# Emmelie-v3_2.net
KiCad netlist of a schematic drawn in EAGLE
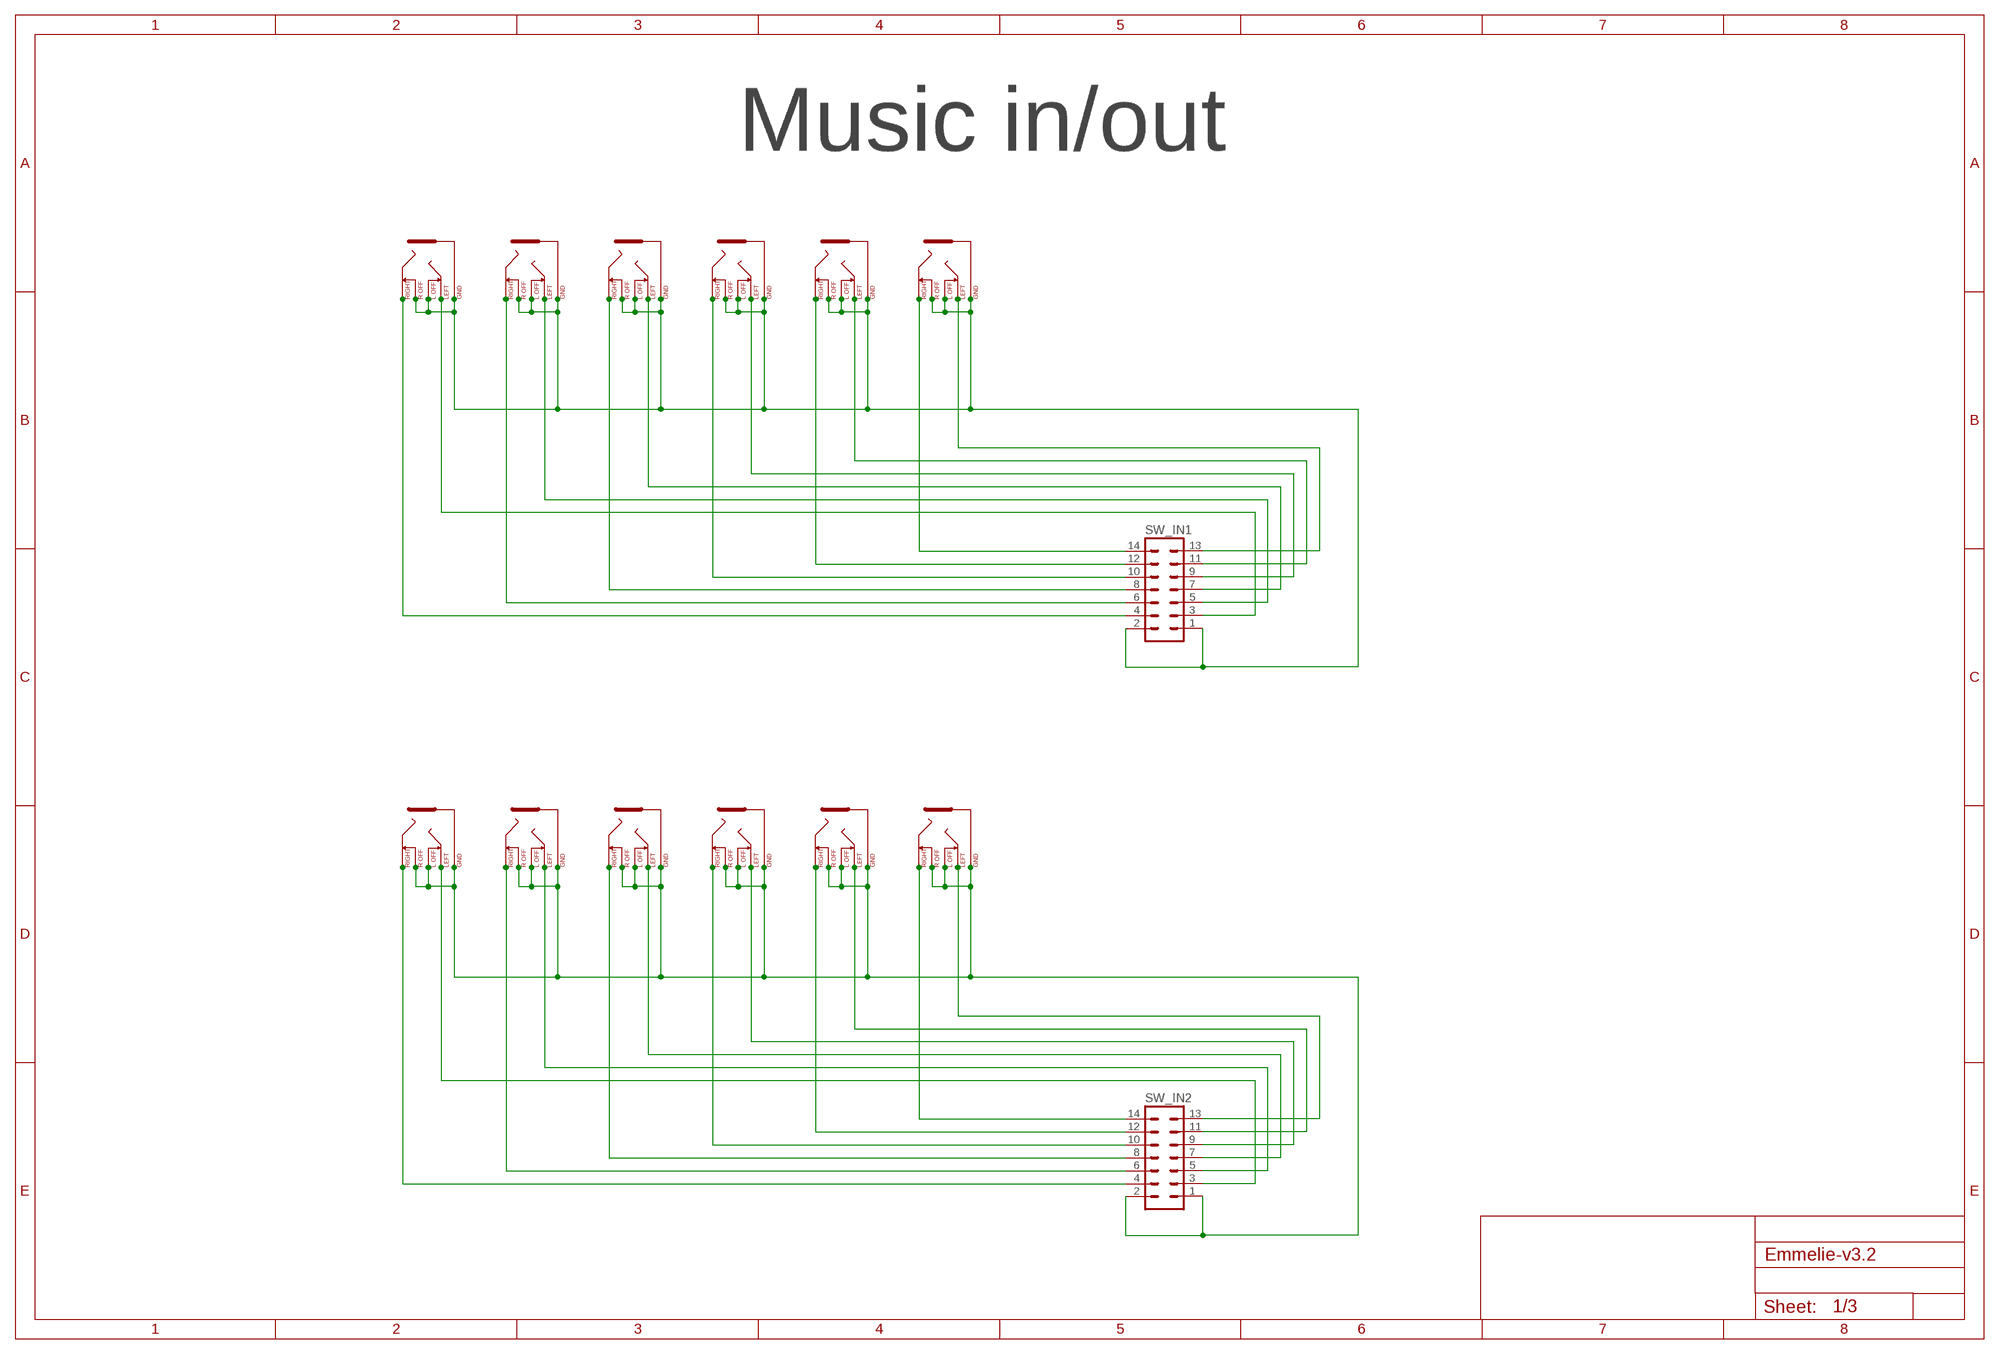
[diagram p0: schematic, sheet 1]
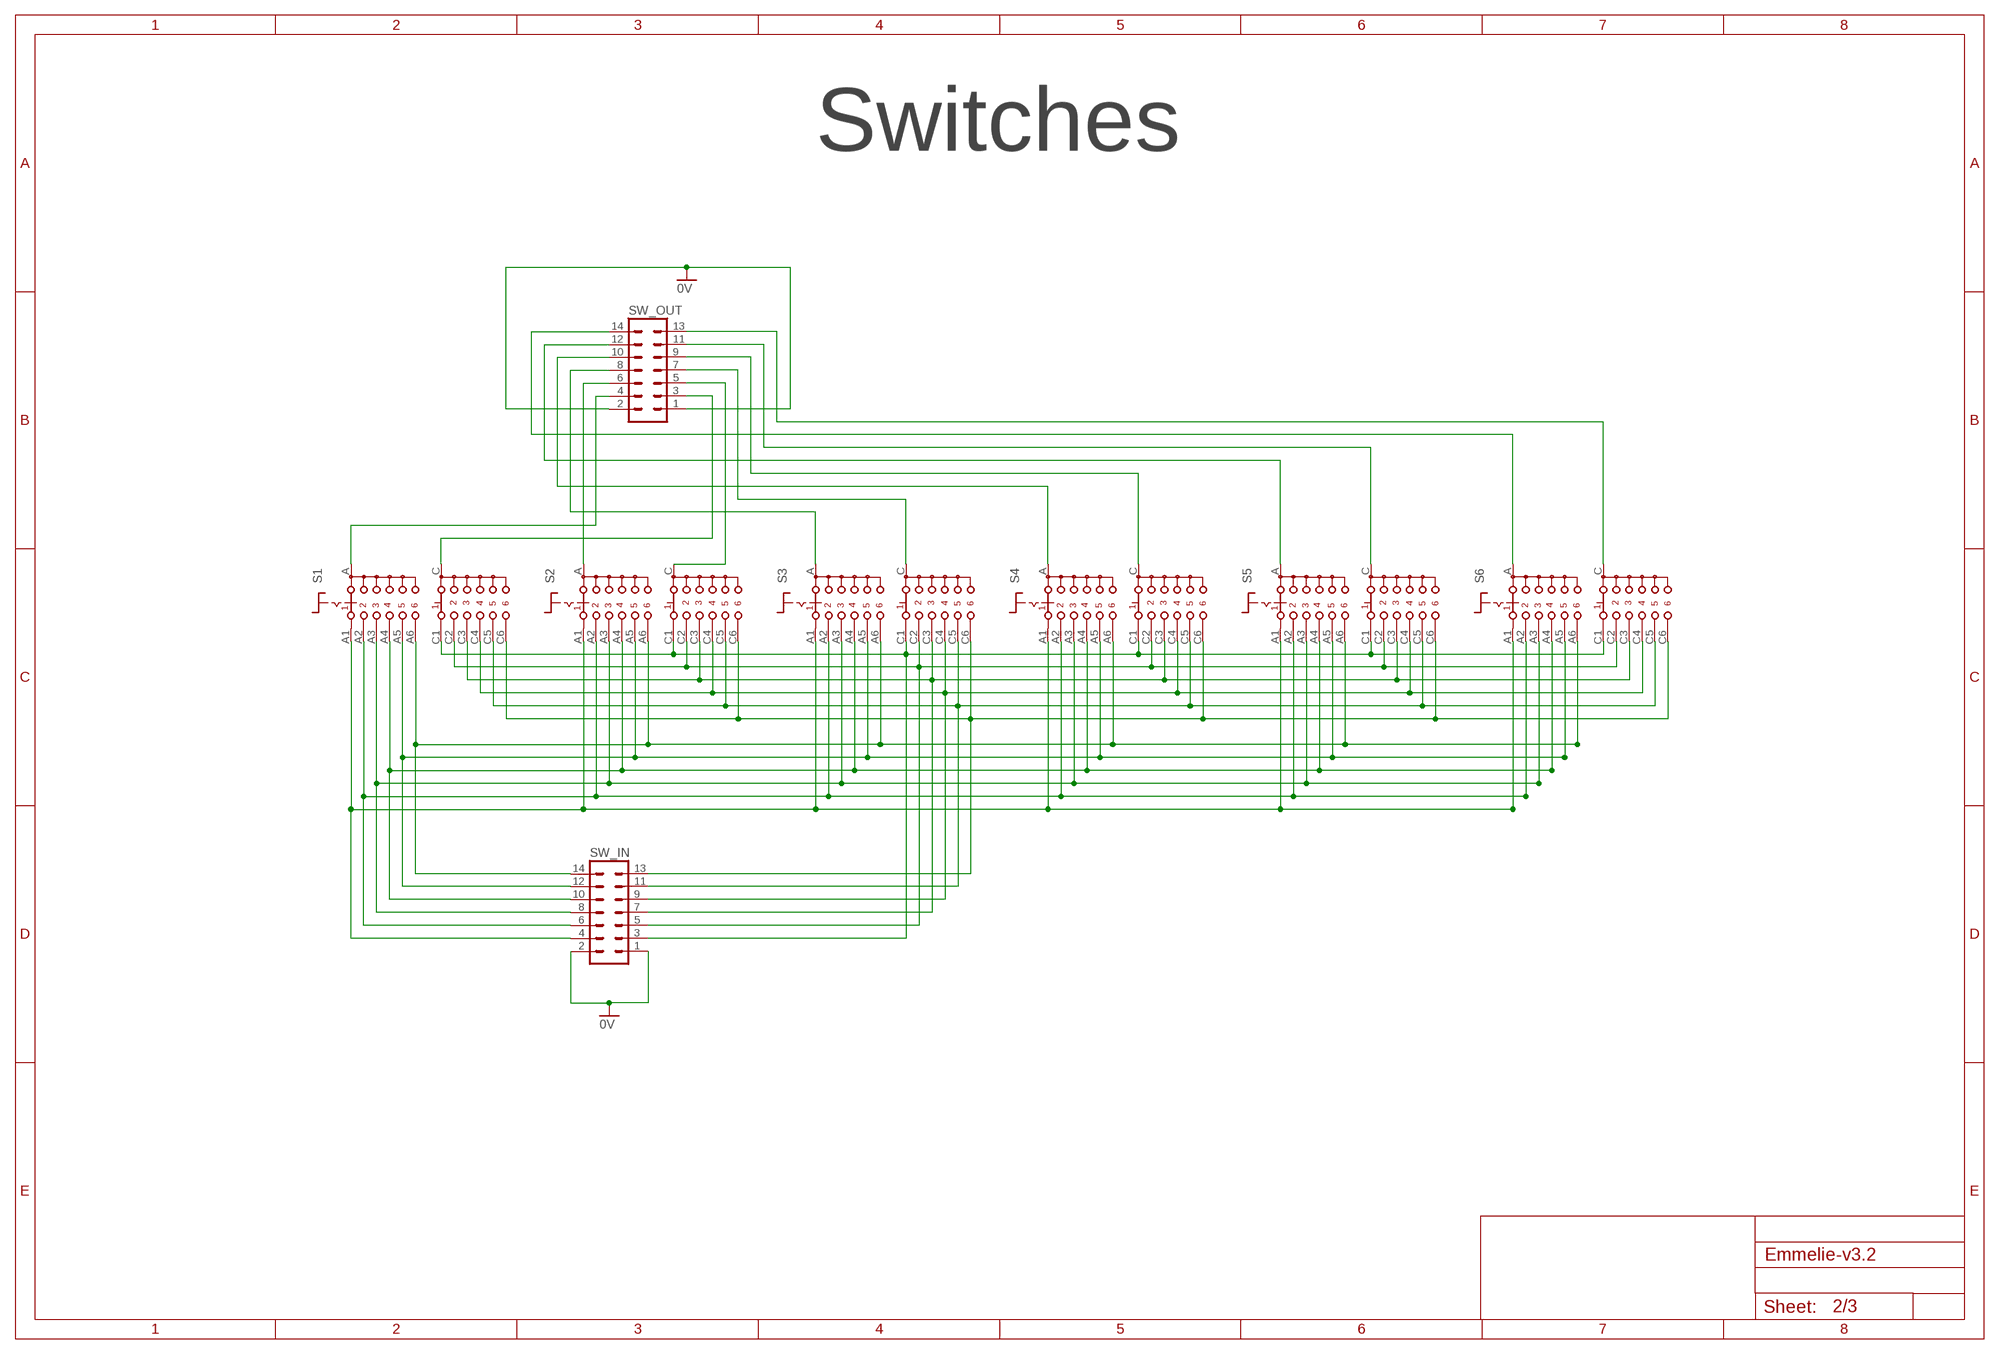
[diagram p1: schematic, sheet 2]
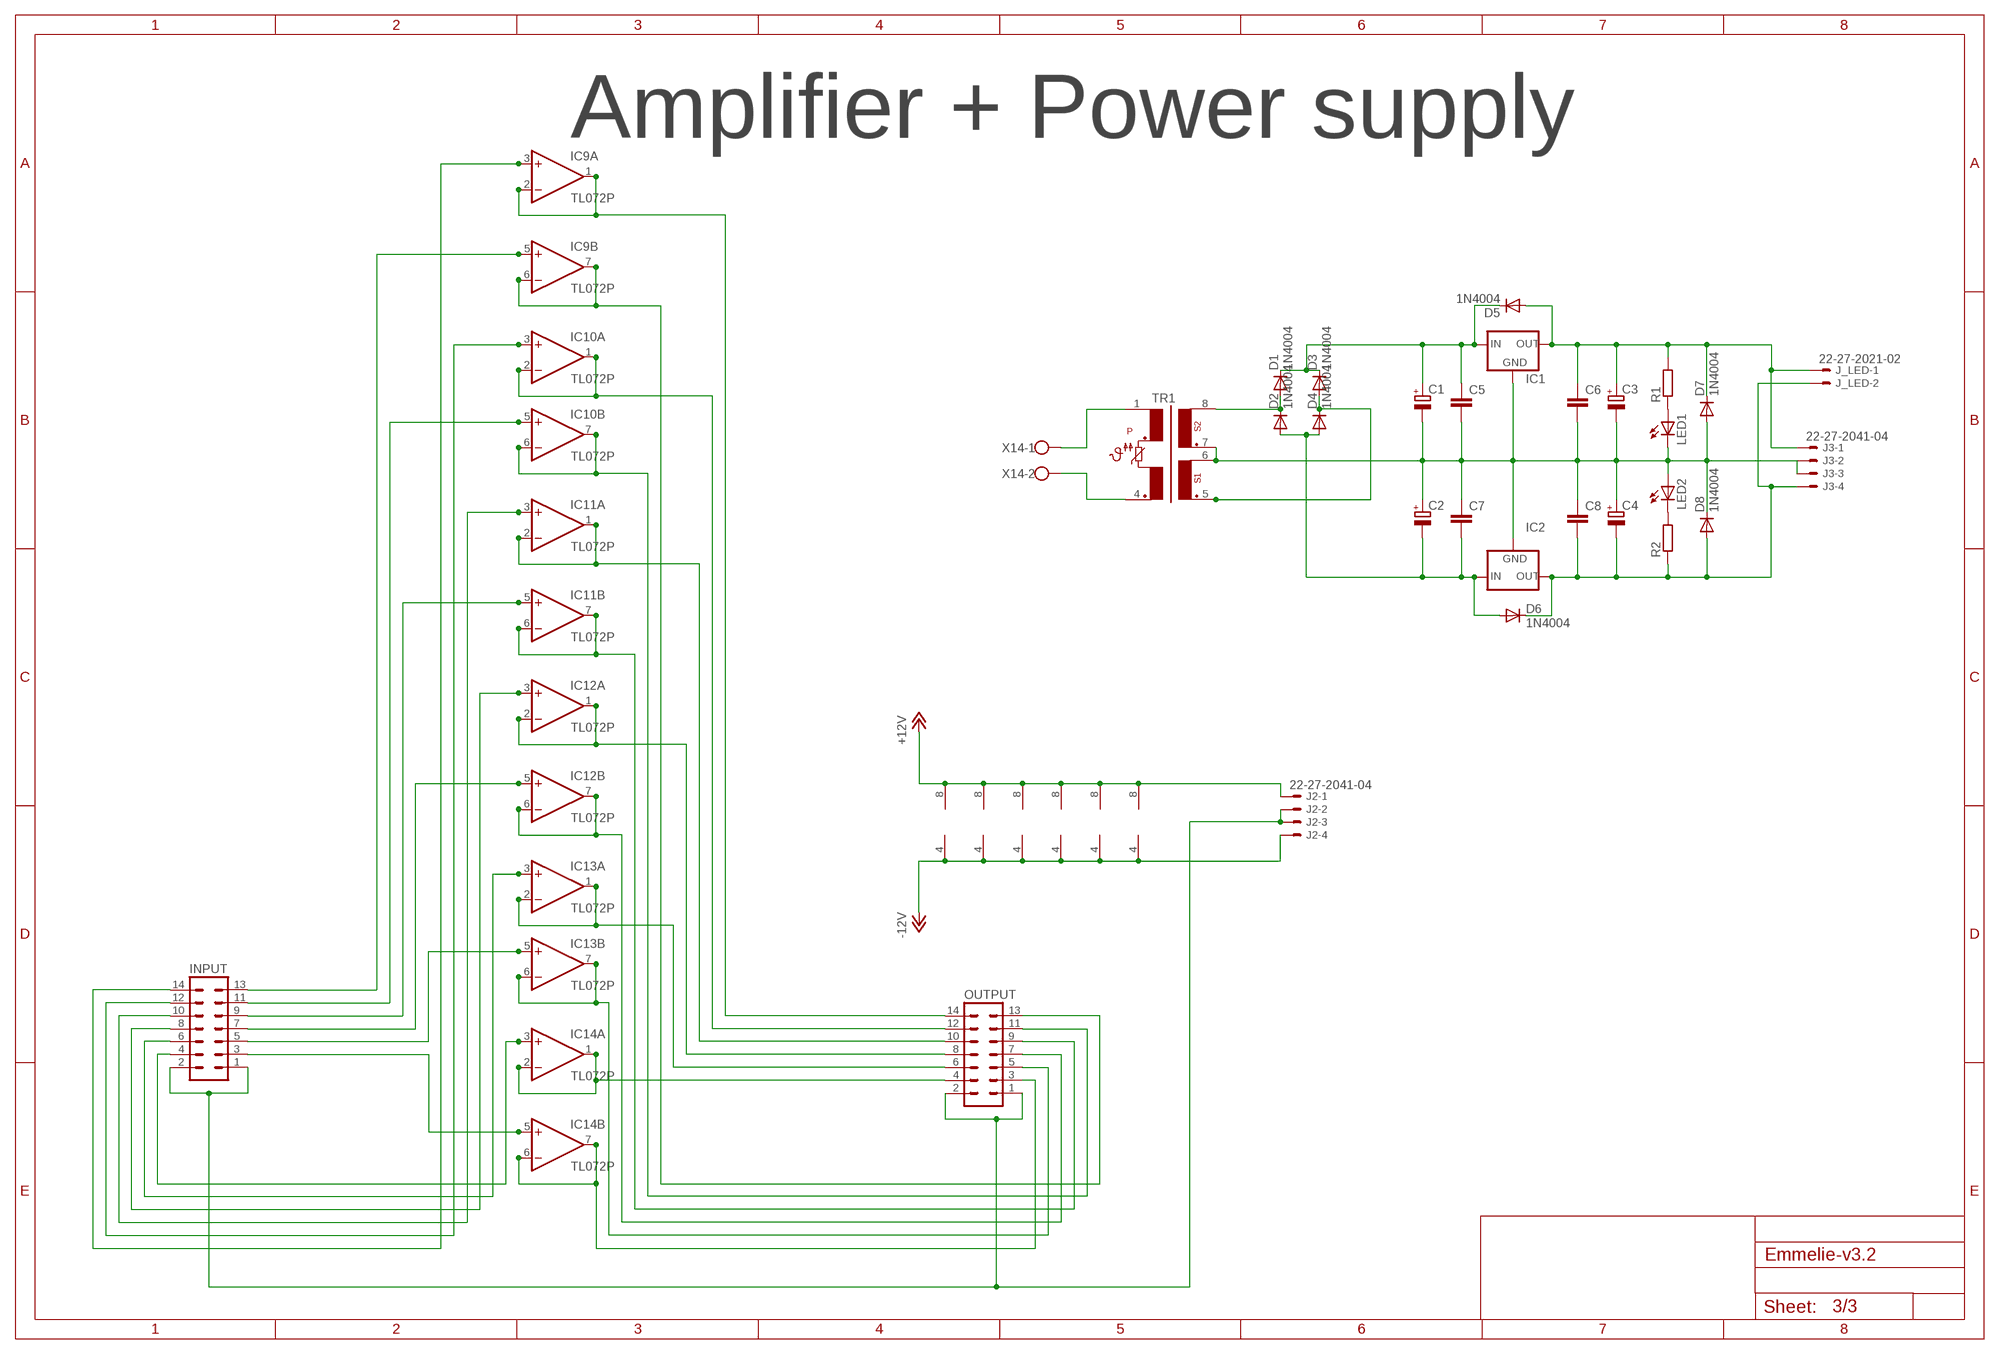
[diagram p2: schematic, sheet 3]

(export (version "E")
  (design (tool "Eeschema 10.0.6"))
  (components
    (comp (ref "C1")
      (value "CPOL-EUE5-13")
      (footprint "eagle-import:E5-13")
      (libsource (lib "eagle-import") (part "resistor_CPOL-EUE5-13"))
    )
    (comp (ref "C2")
      (value "CPOL-EUE5-13")
      (footprint "eagle-import:E5-13")
      (libsource (lib "eagle-import") (part "resistor_CPOL-EUE5-13"))
    )
    (comp (ref "C3")
      (value "CPOL-EUE2.5-7")
      (footprint "eagle-import:E2,5-7")
      (libsource (lib "eagle-import") (part "CPOL-EUE2.5-7"))
    )
    (comp (ref "C4")
      (value "CPOL-EUE2.5-7")
      (footprint "eagle-import:E2,5-7")
      (libsource (lib "eagle-import") (part "CPOL-EUE2.5-7"))
    )
    (comp (ref "C5")
      (value "C-EU050-075X075")
      (footprint "eagle-import:C050-075X075")
      (libsource (lib "eagle-import") (part "C-EU050-075X075"))
    )
    (comp (ref "C6")
      (value "C-EU050-075X075")
      (footprint "eagle-import:C050-075X075")
      (libsource (lib "eagle-import") (part "C-EU050-075X075"))
    )
    (comp (ref "C7")
      (value "C-EU050-075X075")
      (footprint "eagle-import:C050-075X075")
      (libsource (lib "eagle-import") (part "C-EU050-075X075"))
    )
    (comp (ref "C8")
      (value "C-EU050-075X075")
      (footprint "eagle-import:C050-075X075")
      (libsource (lib "eagle-import") (part "C-EU050-075X075"))
    )
    (comp (ref "D1")
      (value "1N4004")
      (footprint "eagle-import:DO41-10")
      (libsource (lib "eagle-import") (part "1N4004"))
    )
    (comp (ref "D2")
      (value "1N4004")
      (footprint "eagle-import:DO41-10")
      (libsource (lib "eagle-import") (part "1N4004"))
    )
    (comp (ref "D3")
      (value "1N4004")
      (footprint "eagle-import:DO41-10")
      (libsource (lib "eagle-import") (part "1N4004"))
    )
    (comp (ref "D4")
      (value "1N4004")
      (footprint "eagle-import:DO41-10")
      (libsource (lib "eagle-import") (part "1N4004"))
    )
    (comp (ref "D5")
      (value "1N4004")
      (footprint "eagle-import:DO41-10")
      (libsource (lib "eagle-import") (part "1N4004"))
    )
    (comp (ref "D6")
      (value "1N4004")
      (footprint "eagle-import:DO41-10")
      (libsource (lib "eagle-import") (part "1N4004"))
    )
    (comp (ref "D7")
      (value "1N4004")
      (footprint "eagle-import:DO41-10")
      (libsource (lib "eagle-import") (part "1N4004"))
    )
    (comp (ref "D8")
      (value "1N4004")
      (footprint "eagle-import:DO41-10")
      (libsource (lib "eagle-import") (part "1N4004"))
    )
    (comp (ref "IC1")
      (value "78XXS")
      (footprint "eagle-import:78XXS")
      (libsource (lib "eagle-import") (part "78XXS"))
    )
    (comp (ref "IC2")
      (value "79XXS")
      (footprint "eagle-import:79XXS")
      (libsource (lib "eagle-import") (part "79XXS"))
    )
    (comp (ref "IC9")
      (value "TL072P")
      (footprint "eagle-import:DIL08")
      (libsource (lib "eagle-import") (part "TL072P"))
    )
    (comp (ref "IC10")
      (value "TL072P")
      (footprint "eagle-import:DIL08")
      (libsource (lib "eagle-import") (part "TL072P"))
    )
    (comp (ref "IC11")
      (value "TL072P")
      (footprint "eagle-import:DIL08")
      (libsource (lib "eagle-import") (part "TL072P"))
    )
    (comp (ref "IC12")
      (value "TL072P")
      (footprint "eagle-import:DIL08")
      (libsource (lib "eagle-import") (part "TL072P"))
    )
    (comp (ref "IC13")
      (value "TL072P")
      (footprint "eagle-import:DIL08")
      (libsource (lib "eagle-import") (part "TL072P"))
    )
    (comp (ref "IC14")
      (value "TL072P")
      (footprint "eagle-import:DIL08")
      (libsource (lib "eagle-import") (part "TL072P"))
    )
    (comp (ref "INPUT")
      (value "ML14")
      (footprint "eagle-import:ML14")
      (libsource (lib "eagle-import") (part "ML14"))
    )
    (comp (ref "J2")
      (value "22-27-2041-04")
      (footprint "eagle-import:6410-04")
      (libsource (lib "eagle-import") (part "22-?-0427-2041"))
    )
    (comp (ref "J3")
      (value "22-27-2041-04")
      (footprint "eagle-import:6410-04")
      (libsource (lib "eagle-import") (part "22-?-0427-2041"))
    )
    (comp (ref "J_LED")
      (value "22-27-2021-02")
      (footprint "eagle-import:6410-02")
      (libsource (lib "eagle-import") (part "22-?-0227-2021"))
    )
    (comp (ref "LED1")
      (value "LED5MM")
      (footprint "eagle-import:LED5MM")
      (libsource (lib "eagle-import") (part "LED5MM"))
    )
    (comp (ref "LED2")
      (value "LED5MM")
      (footprint "eagle-import:LED5MM")
      (libsource (lib "eagle-import") (part "LED5MM"))
    )
    (comp (ref "OUTPUT")
      (value "ML14")
      (footprint "eagle-import:ML14")
      (libsource (lib "eagle-import") (part "ML14"))
    )
    (comp (ref "R1")
      (value "R-EU_0207/15")
      (footprint "eagle-import:0207_15")
      (libsource (lib "eagle-import") (part "R-EU_0207/15"))
    )
    (comp (ref "R2")
      (value "R-EU_0207/15")
      (footprint "eagle-import:0207_15")
      (libsource (lib "eagle-import") (part "R-EU_0207/15"))
    )
    (comp (ref "TR1")
      (value "FLE04-06")
      (footprint "eagle-import:FLE04-06")
      (libsource (lib "eagle-import") (part "FLE04-06"))
    )
    (comp (ref "X14")
      (value "W237-02P")
      (footprint "eagle-import:W237-132")
      (libsource (lib "eagle-import") (part "W237-02P"))
    )
    (comp (ref "SW_IN1")
      (value "ML14")
      (footprint "eagle-import:ML14")
      (libsource (lib "eagle-import") (part "ML14"))
    )
    (comp (ref "SW_IN2")
      (value "ML14")
      (footprint "eagle-import:ML14")
      (libsource (lib "eagle-import") (part "ML14"))
    )
    (comp (ref "U$1")
      (value "KLINKE3,5")
      (footprint "eagle-import:KLINKE3,5")
      (libsource (lib "eagle-import") (part "KLINKE3,5"))
    )
    (comp (ref "U$2")
      (value "KLINKE3,5")
      (footprint "eagle-import:KLINKE3,5")
      (libsource (lib "eagle-import") (part "KLINKE3,5"))
    )
    (comp (ref "U$3")
      (value "KLINKE3,5")
      (footprint "eagle-import:KLINKE3,5")
      (libsource (lib "eagle-import") (part "KLINKE3,5"))
    )
    (comp (ref "U$4")
      (value "KLINKE3,5")
      (footprint "eagle-import:KLINKE3,5")
      (libsource (lib "eagle-import") (part "KLINKE3,5"))
    )
    (comp (ref "U$5")
      (value "KLINKE3,5")
      (footprint "eagle-import:KLINKE3,5")
      (libsource (lib "eagle-import") (part "KLINKE3,5"))
    )
    (comp (ref "U$6")
      (value "KLINKE3,5")
      (footprint "eagle-import:KLINKE3,5")
      (libsource (lib "eagle-import") (part "KLINKE3,5"))
    )
    (comp (ref "U$7")
      (value "KLINKE3,5")
      (footprint "eagle-import:KLINKE3,5")
      (libsource (lib "eagle-import") (part "KLINKE3,5"))
    )
    (comp (ref "U$8")
      (value "KLINKE3,5")
      (footprint "eagle-import:KLINKE3,5")
      (libsource (lib "eagle-import") (part "KLINKE3,5"))
    )
    (comp (ref "U$9")
      (value "KLINKE3,5")
      (footprint "eagle-import:KLINKE3,5")
      (libsource (lib "eagle-import") (part "KLINKE3,5"))
    )
    (comp (ref "U$10")
      (value "KLINKE3,5")
      (footprint "eagle-import:KLINKE3,5")
      (libsource (lib "eagle-import") (part "KLINKE3,5"))
    )
    (comp (ref "U$11")
      (value "KLINKE3,5")
      (footprint "eagle-import:KLINKE3,5")
      (libsource (lib "eagle-import") (part "KLINKE3,5"))
    )
    (comp (ref "U$12")
      (value "KLINKE3,5")
      (footprint "eagle-import:KLINKE3,5")
      (libsource (lib "eagle-import") (part "KLINKE3,5"))
    )
    (comp (ref "S1")
      (value "CK102X06")
      (footprint "eagle-import:CK102X06")
      (libsource (lib "eagle-import") (part "CK102X06"))
    )
    (comp (ref "S2")
      (value "CK102X06")
      (footprint "eagle-import:CK102X06")
      (libsource (lib "eagle-import") (part "CK102X06"))
    )
    (comp (ref "S3")
      (value "CK102X06")
      (footprint "eagle-import:CK102X06")
      (libsource (lib "eagle-import") (part "CK102X06"))
    )
    (comp (ref "S4")
      (value "CK102X06")
      (footprint "eagle-import:CK102X06")
      (libsource (lib "eagle-import") (part "CK102X06"))
    )
    (comp (ref "S5")
      (value "CK102X06")
      (footprint "eagle-import:CK102X06")
      (libsource (lib "eagle-import") (part "CK102X06"))
    )
    (comp (ref "S6")
      (value "CK102X06")
      (footprint "eagle-import:CK102X06")
      (libsource (lib "eagle-import") (part "CK102X06"))
    )
    (comp (ref "SW_IN")
      (value "ML14")
      (footprint "eagle-import:ML14")
      (libsource (lib "eagle-import") (part "ML14"))
    )
    (comp (ref "SW_OUT")
      (value "ML14")
      (footprint "eagle-import:ML14")
      (libsource (lib "eagle-import") (part "ML14"))
    )
  )
  (nets
    (net (code "1") (name "+12V") (class "Default")
      (node (ref "IC10") (pin "8") (pinfunction "V+_8") (pintype "power_in"))
      (node (ref "IC11") (pin "8") (pinfunction "V+_8") (pintype "power_in"))
      (node (ref "IC12") (pin "8") (pinfunction "V+_8") (pintype "power_in"))
      (node (ref "IC13") (pin "8") (pinfunction "V+_8") (pintype "power_in"))
      (node (ref "IC14") (pin "8") (pinfunction "V+_8") (pintype "power_in"))
      (node (ref "IC9") (pin "8") (pinfunction "V+_8") (pintype "power_in"))
      (node (ref "J2") (pin "1") (pinfunction "S_1") (pintype "passive"))
    )
    (net (code "2") (name "-12V") (class "Default")
      (node (ref "IC10") (pin "4") (pinfunction "V-_4") (pintype "power_in"))
      (node (ref "IC11") (pin "4") (pinfunction "V-_4") (pintype "power_in"))
      (node (ref "IC12") (pin "4") (pinfunction "V-_4") (pintype "power_in"))
      (node (ref "IC13") (pin "4") (pinfunction "V-_4") (pintype "power_in"))
      (node (ref "IC14") (pin "4") (pinfunction "V-_4") (pintype "power_in"))
      (node (ref "IC9") (pin "4") (pinfunction "V-_4") (pintype "power_in"))
      (node (ref "J2") (pin "4") (pinfunction "S_4") (pintype "passive"))
    )
    (net (code "3") (name "0V") (class "Default")
      (node (ref "SW_IN") (pin "1") (pinfunction "1_1") (pintype "passive"))
      (node (ref "SW_IN") (pin "2") (pinfunction "2_2") (pintype "passive"))
      (node (ref "SW_OUT") (pin "1") (pinfunction "1_1") (pintype "passive"))
      (node (ref "SW_OUT") (pin "2") (pinfunction "2_2") (pintype "passive"))
    )
    (net (code "4") (name "Net-(C1-Pad+)") (class "Default")
      (node (ref "C1") (pin "+") (pinfunction "+_+") (pintype "passive"))
      (node (ref "C5") (pin "1") (pinfunction "1_1") (pintype "passive"))
      (node (ref "D1") (pin "C") (pinfunction "C_C") (pintype "passive"))
      (node (ref "D3") (pin "C") (pinfunction "C_C") (pintype "passive"))
      (node (ref "D5") (pin "C") (pinfunction "C_C") (pintype "passive"))
      (node (ref "IC1") (pin "IN") (pinfunction "IN_IN") (pintype "input"))
    )
    (net (code "5") (name "Net-(C2-Pad-)") (class "Default")
      (node (ref "C2") (pin "-") (pinfunction "-_-") (pintype "passive"))
      (node (ref "C7") (pin "2") (pinfunction "2_2") (pintype "passive"))
      (node (ref "D2") (pin "A") (pinfunction "A_A") (pintype "passive"))
      (node (ref "D4") (pin "A") (pinfunction "A_A") (pintype "passive"))
      (node (ref "D6") (pin "A") (pinfunction "A_A") (pintype "passive"))
      (node (ref "IC2") (pin "IN") (pinfunction "IN_IN") (pintype "input"))
    )
    (net (code "6") (name "Net-(D1-PadA)") (class "Default")
      (node (ref "D1") (pin "A") (pinfunction "A_A") (pintype "passive"))
      (node (ref "D2") (pin "C") (pinfunction "C_C") (pintype "passive"))
      (node (ref "TR1") (pin "8") (pinfunction "8_8") (pintype "passive"))
    )
    (net (code "7") (name "Net-(D3-PadA)") (class "Default")
      (node (ref "D3") (pin "A") (pinfunction "A_A") (pintype "passive"))
      (node (ref "D4") (pin "C") (pinfunction "C_C") (pintype "passive"))
      (node (ref "TR1") (pin "5") (pinfunction "5_5") (pintype "passive"))
    )
    (net (code "8") (name "Net-(IC9A-+IN)") (class "Default")
      (node (ref "IC9") (pin "3") (pinfunction "+IN_3") (pintype "input"))
      (node (ref "INPUT") (pin "14") (pinfunction "14_14") (pintype "passive"))
    )
    (net (code "9") (name "Net-(IC9A--IN)") (class "Default")
      (node (ref "IC9") (pin "1") (pinfunction "OUT_1") (pintype "output"))
      (node (ref "IC9") (pin "2") (pinfunction "-IN_2") (pintype "input"))
      (node (ref "OUTPUT") (pin "14") (pinfunction "14_14") (pintype "passive"))
    )
    (net (code "10") (name "Net-(IC9B-+IN)") (class "Default")
      (node (ref "IC9") (pin "5") (pinfunction "+IN_5") (pintype "input"))
      (node (ref "INPUT") (pin "13") (pinfunction "13_13") (pintype "passive"))
    )
    (net (code "11") (name "Net-(IC9B--IN)") (class "Default")
      (node (ref "IC9") (pin "6") (pinfunction "-IN_6") (pintype "input"))
      (node (ref "IC9") (pin "7") (pinfunction "OUT_7") (pintype "output"))
      (node (ref "OUTPUT") (pin "13") (pinfunction "13_13") (pintype "passive"))
    )
    (net (code "12") (name "Net-(IC10A-+IN)") (class "Default")
      (node (ref "IC10") (pin "3") (pinfunction "+IN_3") (pintype "input"))
      (node (ref "INPUT") (pin "12") (pinfunction "12_12") (pintype "passive"))
    )
    (net (code "13") (name "Net-(IC10A--IN)") (class "Default")
      (node (ref "IC10") (pin "1") (pinfunction "OUT_1") (pintype "output"))
      (node (ref "IC10") (pin "2") (pinfunction "-IN_2") (pintype "input"))
      (node (ref "OUTPUT") (pin "12") (pinfunction "12_12") (pintype "passive"))
    )
    (net (code "14") (name "Net-(IC10B-+IN)") (class "Default")
      (node (ref "IC10") (pin "5") (pinfunction "+IN_5") (pintype "input"))
      (node (ref "INPUT") (pin "11") (pinfunction "11_11") (pintype "passive"))
    )
    (net (code "15") (name "Net-(IC10B--IN)") (class "Default")
      (node (ref "IC10") (pin "6") (pinfunction "-IN_6") (pintype "input"))
      (node (ref "IC10") (pin "7") (pinfunction "OUT_7") (pintype "output"))
      (node (ref "OUTPUT") (pin "11") (pinfunction "11_11") (pintype "passive"))
    )
    (net (code "16") (name "Net-(IC11A-+IN)") (class "Default")
      (node (ref "IC11") (pin "3") (pinfunction "+IN_3") (pintype "input"))
      (node (ref "INPUT") (pin "10") (pinfunction "10_10") (pintype "passive"))
    )
    (net (code "17") (name "Net-(IC11A--IN)") (class "Default")
      (node (ref "IC11") (pin "1") (pinfunction "OUT_1") (pintype "output"))
      (node (ref "IC11") (pin "2") (pinfunction "-IN_2") (pintype "input"))
      (node (ref "OUTPUT") (pin "10") (pinfunction "10_10") (pintype "passive"))
    )
    (net (code "18") (name "Net-(IC11B-+IN)") (class "Default")
      (node (ref "IC11") (pin "5") (pinfunction "+IN_5") (pintype "input"))
      (node (ref "INPUT") (pin "9") (pinfunction "9_9") (pintype "passive"))
    )
    (net (code "19") (name "Net-(IC11B--IN)") (class "Default")
      (node (ref "IC11") (pin "6") (pinfunction "-IN_6") (pintype "input"))
      (node (ref "IC11") (pin "7") (pinfunction "OUT_7") (pintype "output"))
      (node (ref "OUTPUT") (pin "9") (pinfunction "9_9") (pintype "passive"))
    )
    (net (code "20") (name "Net-(IC12A-+IN)") (class "Default")
      (node (ref "IC12") (pin "3") (pinfunction "+IN_3") (pintype "input"))
      (node (ref "INPUT") (pin "8") (pinfunction "8_8") (pintype "passive"))
    )
    (net (code "21") (name "Net-(IC12A--IN)") (class "Default")
      (node (ref "IC12") (pin "1") (pinfunction "OUT_1") (pintype "output"))
      (node (ref "IC12") (pin "2") (pinfunction "-IN_2") (pintype "input"))
      (node (ref "OUTPUT") (pin "8") (pinfunction "8_8") (pintype "passive"))
    )
    (net (code "22") (name "Net-(IC12B-+IN)") (class "Default")
      (node (ref "IC12") (pin "5") (pinfunction "+IN_5") (pintype "input"))
      (node (ref "INPUT") (pin "7") (pinfunction "7_7") (pintype "passive"))
    )
    (net (code "23") (name "Net-(IC12B--IN)") (class "Default")
      (node (ref "IC12") (pin "6") (pinfunction "-IN_6") (pintype "input"))
      (node (ref "IC12") (pin "7") (pinfunction "OUT_7") (pintype "output"))
      (node (ref "OUTPUT") (pin "7") (pinfunction "7_7") (pintype "passive"))
    )
    (net (code "24") (name "Net-(IC13A-+IN)") (class "Default")
      (node (ref "IC13") (pin "3") (pinfunction "+IN_3") (pintype "input"))
      (node (ref "INPUT") (pin "6") (pinfunction "6_6") (pintype "passive"))
    )
    (net (code "25") (name "Net-(IC13A--IN)") (class "Default")
      (node (ref "IC13") (pin "1") (pinfunction "OUT_1") (pintype "output"))
      (node (ref "IC13") (pin "2") (pinfunction "-IN_2") (pintype "input"))
      (node (ref "OUTPUT") (pin "6") (pinfunction "6_6") (pintype "passive"))
    )
    (net (code "26") (name "Net-(IC13B-+IN)") (class "Default")
      (node (ref "IC13") (pin "5") (pinfunction "+IN_5") (pintype "input"))
      (node (ref "INPUT") (pin "5") (pinfunction "5_5") (pintype "passive"))
    )
    (net (code "27") (name "Net-(IC13B--IN)") (class "Default")
      (node (ref "IC13") (pin "6") (pinfunction "-IN_6") (pintype "input"))
      (node (ref "IC13") (pin "7") (pinfunction "OUT_7") (pintype "output"))
      (node (ref "OUTPUT") (pin "5") (pinfunction "5_5") (pintype "passive"))
    )
    (net (code "28") (name "Net-(IC14A-+IN)") (class "Default")
      (node (ref "IC14") (pin "3") (pinfunction "+IN_3") (pintype "input"))
      (node (ref "INPUT") (pin "4") (pinfunction "4_4") (pintype "passive"))
    )
    (net (code "29") (name "Net-(IC14A--IN)") (class "Default")
      (node (ref "IC14") (pin "1") (pinfunction "OUT_1") (pintype "output"))
      (node (ref "IC14") (pin "2") (pinfunction "-IN_2") (pintype "input"))
      (node (ref "OUTPUT") (pin "4") (pinfunction "4_4") (pintype "passive"))
    )
    (net (code "30") (name "Net-(IC14B-+IN)") (class "Default")
      (node (ref "IC14") (pin "5") (pinfunction "+IN_5") (pintype "input"))
      (node (ref "INPUT") (pin "3") (pinfunction "3_3") (pintype "passive"))
    )
    (net (code "31") (name "Net-(IC14B--IN)") (class "Default")
      (node (ref "IC14") (pin "6") (pinfunction "-IN_6") (pintype "input"))
      (node (ref "IC14") (pin "7") (pinfunction "OUT_7") (pintype "output"))
      (node (ref "OUTPUT") (pin "3") (pinfunction "3_3") (pintype "passive"))
    )
    (net (code "32") (name "Net-(J2B-S)") (class "Default")
      (node (ref "INPUT") (pin "1") (pinfunction "1_1") (pintype "passive"))
      (node (ref "INPUT") (pin "2") (pinfunction "2_2") (pintype "passive"))
      (node (ref "J2") (pin "2") (pinfunction "S_2") (pintype "passive"))
      (node (ref "J2") (pin "3") (pinfunction "S_3") (pintype "passive"))
      (node (ref "OUTPUT") (pin "1") (pinfunction "1_1") (pintype "passive"))
      (node (ref "OUTPUT") (pin "2") (pinfunction "2_2") (pintype "passive"))
    )
    (net (code "33") (name "Net-(J3A-S)") (class "Default")
      (node (ref "C3") (pin "+") (pinfunction "+_+") (pintype "passive"))
      (node (ref "C6") (pin "1") (pinfunction "1_1") (pintype "passive"))
      (node (ref "D5") (pin "A") (pinfunction "A_A") (pintype "passive"))
      (node (ref "D7") (pin "C") (pinfunction "C_C") (pintype "passive"))
      (node (ref "IC1") (pin "OUT") (pinfunction "OUT_OUT") (pintype "passive"))
      (node (ref "J3") (pin "1") (pinfunction "S_1") (pintype "passive"))
      (node (ref "J_LED") (pin "1") (pinfunction "S_1") (pintype "passive"))
      (node (ref "R1") (pin "2") (pinfunction "2_2") (pintype "passive"))
    )
    (net (code "34") (name "Net-(J3B-S)") (class "Default")
      (node (ref "C1") (pin "-") (pinfunction "-_-") (pintype "passive"))
      (node (ref "C2") (pin "+") (pinfunction "+_+") (pintype "passive"))
      (node (ref "C3") (pin "-") (pinfunction "-_-") (pintype "passive"))
      (node (ref "C4") (pin "+") (pinfunction "+_+") (pintype "passive"))
      (node (ref "C5") (pin "2") (pinfunction "2_2") (pintype "passive"))
      (node (ref "C6") (pin "2") (pinfunction "2_2") (pintype "passive"))
      (node (ref "C7") (pin "1") (pinfunction "1_1") (pintype "passive"))
      (node (ref "C8") (pin "1") (pinfunction "1_1") (pintype "passive"))
      (node (ref "D7") (pin "A") (pinfunction "A_A") (pintype "passive"))
      (node (ref "D8") (pin "C") (pinfunction "C_C") (pintype "passive"))
      (node (ref "IC1") (pin "GND") (pinfunction "GND_GND") (pintype "input"))
      (node (ref "IC2") (pin "GND") (pinfunction "GND_GND") (pintype "input"))
      (node (ref "J3") (pin "2") (pinfunction "S_2") (pintype "passive"))
      (node (ref "J3") (pin "3") (pinfunction "S_3") (pintype "passive"))
      (node (ref "LED1") (pin "K") (pinfunction "C_K") (pintype "passive"))
      (node (ref "LED2") (pin "A") (pinfunction "A_A") (pintype "passive"))
      (node (ref "TR1") (pin "6") (pinfunction "6_6") (pintype "passive"))
      (node (ref "TR1") (pin "7") (pinfunction "7_7") (pintype "passive"))
    )
    (net (code "35") (name "Net-(J3D-S)") (class "Default")
      (node (ref "C4") (pin "-") (pinfunction "-_-") (pintype "passive"))
      (node (ref "C8") (pin "2") (pinfunction "2_2") (pintype "passive"))
      (node (ref "D6") (pin "C") (pinfunction "C_C") (pintype "passive"))
      (node (ref "D8") (pin "A") (pinfunction "A_A") (pintype "passive"))
      (node (ref "IC2") (pin "OUT") (pinfunction "OUT_OUT") (pintype "passive"))
      (node (ref "J3") (pin "4") (pinfunction "S_4") (pintype "passive"))
      (node (ref "J_LED") (pin "2") (pinfunction "S_2") (pintype "passive"))
      (node (ref "R2") (pin "1") (pinfunction "1_1") (pintype "passive"))
    )
    (net (code "36") (name "Net-(LED1-PadA)") (class "Default")
      (node (ref "LED1") (pin "A") (pinfunction "A_A") (pintype "passive"))
      (node (ref "R1") (pin "1") (pinfunction "1_1") (pintype "passive"))
    )
    (net (code "37") (name "Net-(LED2-C)") (class "Default")
      (node (ref "LED2") (pin "K") (pinfunction "C_K") (pintype "passive"))
      (node (ref "R2") (pin "2") (pinfunction "2_2") (pintype "passive"))
    )
    (net (code "38") (name "Net-(S1-PadA)") (class "Default")
      (node (ref "S1") (pin "A") (pinfunction "A_A") (pintype "passive"))
      (node (ref "SW_OUT") (pin "4") (pinfunction "4_4") (pintype "passive"))
    )
    (net (code "39") (name "Net-(S1-PadA1)") (class "Default")
      (node (ref "S1") (pin "A1") (pinfunction "A1_A1") (pintype "passive"))
      (node (ref "S2") (pin "A1") (pinfunction "A1_A1") (pintype "passive"))
      (node (ref "S3") (pin "A1") (pinfunction "A1_A1") (pintype "passive"))
      (node (ref "S4") (pin "A1") (pinfunction "A1_A1") (pintype "passive"))
      (node (ref "S5") (pin "A1") (pinfunction "A1_A1") (pintype "passive"))
      (node (ref "S6") (pin "A1") (pinfunction "A1_A1") (pintype "passive"))
      (node (ref "SW_IN") (pin "4") (pinfunction "4_4") (pintype "passive"))
    )
    (net (code "40") (name "Net-(S1-PadA2)") (class "Default")
      (node (ref "S1") (pin "A2") (pinfunction "A2_A2") (pintype "passive"))
      (node (ref "S2") (pin "A2") (pinfunction "A2_A2") (pintype "passive"))
      (node (ref "S3") (pin "A2") (pinfunction "A2_A2") (pintype "passive"))
      (node (ref "S4") (pin "A2") (pinfunction "A2_A2") (pintype "passive"))
      (node (ref "S5") (pin "A2") (pinfunction "A2_A2") (pintype "passive"))
      (node (ref "S6") (pin "A2") (pinfunction "A2_A2") (pintype "passive"))
      (node (ref "SW_IN") (pin "6") (pinfunction "6_6") (pintype "passive"))
    )
    (net (code "41") (name "Net-(S1-PadA3)") (class "Default")
      (node (ref "S1") (pin "A3") (pinfunction "A3_A3") (pintype "passive"))
      (node (ref "S2") (pin "A3") (pinfunction "A3_A3") (pintype "passive"))
      (node (ref "S3") (pin "A3") (pinfunction "A3_A3") (pintype "passive"))
      (node (ref "S4") (pin "A3") (pinfunction "A3_A3") (pintype "passive"))
      (node (ref "S5") (pin "A3") (pinfunction "A3_A3") (pintype "passive"))
      (node (ref "S6") (pin "A3") (pinfunction "A3_A3") (pintype "passive"))
      (node (ref "SW_IN") (pin "8") (pinfunction "8_8") (pintype "passive"))
    )
    (net (code "42") (name "Net-(S1-PadA4)") (class "Default")
      (node (ref "S1") (pin "A4") (pinfunction "A4_A4") (pintype "passive"))
      (node (ref "S2") (pin "A4") (pinfunction "A4_A4") (pintype "passive"))
      (node (ref "S3") (pin "A4") (pinfunction "A4_A4") (pintype "passive"))
      (node (ref "S4") (pin "A4") (pinfunction "A4_A4") (pintype "passive"))
      (node (ref "S5") (pin "A4") (pinfunction "A4_A4") (pintype "passive"))
      (node (ref "S6") (pin "A4") (pinfunction "A4_A4") (pintype "passive"))
      (node (ref "SW_IN") (pin "10") (pinfunction "10_10") (pintype "passive"))
    )
    (net (code "43") (name "Net-(S1-PadA5)") (class "Default")
      (node (ref "S1") (pin "A5") (pinfunction "A5_A5") (pintype "passive"))
      (node (ref "S2") (pin "A5") (pinfunction "A5_A5") (pintype "passive"))
      (node (ref "S3") (pin "A5") (pinfunction "A5_A5") (pintype "passive"))
      (node (ref "S4") (pin "A5") (pinfunction "A5_A5") (pintype "passive"))
      (node (ref "S5") (pin "A5") (pinfunction "A5_A5") (pintype "passive"))
      (node (ref "S6") (pin "A5") (pinfunction "A5_A5") (pintype "passive"))
      (node (ref "SW_IN") (pin "12") (pinfunction "12_12") (pintype "passive"))
    )
    (net (code "44") (name "Net-(S1-PadA6)") (class "Default")
      (node (ref "S1") (pin "A6") (pinfunction "A6_A6") (pintype "passive"))
      (node (ref "S2") (pin "A6") (pinfunction "A6_A6") (pintype "passive"))
      (node (ref "S3") (pin "A6") (pinfunction "A6_A6") (pintype "passive"))
      (node (ref "S4") (pin "A6") (pinfunction "A6_A6") (pintype "passive"))
      (node (ref "S5") (pin "A6") (pinfunction "A6_A6") (pintype "passive"))
      (node (ref "S6") (pin "A6") (pinfunction "A6_A6") (pintype "passive"))
      (node (ref "SW_IN") (pin "14") (pinfunction "14_14") (pintype "passive"))
    )
    (net (code "45") (name "Net-(S1-PadC)") (class "Default")
      (node (ref "S1") (pin "C") (pinfunction "C_C") (pintype "passive"))
      (node (ref "SW_OUT") (pin "3") (pinfunction "3_3") (pintype "passive"))
    )
    (net (code "46") (name "Net-(S1-PadC1)") (class "Default")
      (node (ref "S1") (pin "C1") (pinfunction "C1_C1") (pintype "passive"))
      (node (ref "S2") (pin "C1") (pinfunction "C1_C1") (pintype "passive"))
      (node (ref "S3") (pin "C1") (pinfunction "C1_C1") (pintype "passive"))
      (node (ref "S4") (pin "C1") (pinfunction "C1_C1") (pintype "passive"))
      (node (ref "S5") (pin "C1") (pinfunction "C1_C1") (pintype "passive"))
      (node (ref "S6") (pin "C1") (pinfunction "C1_C1") (pintype "passive"))
      (node (ref "SW_IN") (pin "3") (pinfunction "3_3") (pintype "passive"))
    )
    (net (code "47") (name "Net-(S1-PadC2)") (class "Default")
      (node (ref "S1") (pin "C2") (pinfunction "C2_C2") (pintype "passive"))
      (node (ref "S2") (pin "C2") (pinfunction "C2_C2") (pintype "passive"))
      (node (ref "S3") (pin "C2") (pinfunction "C2_C2") (pintype "passive"))
      (node (ref "S4") (pin "C2") (pinfunction "C2_C2") (pintype "passive"))
      (node (ref "S5") (pin "C2") (pinfunction "C2_C2") (pintype "passive"))
      (node (ref "S6") (pin "C2") (pinfunction "C2_C2") (pintype "passive"))
      (node (ref "SW_IN") (pin "5") (pinfunction "5_5") (pintype "passive"))
    )
    (net (code "48") (name "Net-(S1-PadC3)") (class "Default")
      (node (ref "S1") (pin "C3") (pinfunction "C3_C3") (pintype "passive"))
      (node (ref "S2") (pin "C3") (pinfunction "C3_C3") (pintype "passive"))
      (node (ref "S3") (pin "C3") (pinfunction "C3_C3") (pintype "passive"))
      (node (ref "S4") (pin "C3") (pinfunction "C3_C3") (pintype "passive"))
      (node (ref "S5") (pin "C3") (pinfunction "C3_C3") (pintype "passive"))
      (node (ref "S6") (pin "C3") (pinfunction "C3_C3") (pintype "passive"))
      (node (ref "SW_IN") (pin "7") (pinfunction "7_7") (pintype "passive"))
    )
    (net (code "49") (name "Net-(S1-PadC4)") (class "Default")
      (node (ref "S1") (pin "C4") (pinfunction "C4_C4") (pintype "passive"))
      (node (ref "S2") (pin "C4") (pinfunction "C4_C4") (pintype "passive"))
      (node (ref "S3") (pin "C4") (pinfunction "C4_C4") (pintype "passive"))
      (node (ref "S4") (pin "C4") (pinfunction "C4_C4") (pintype "passive"))
      (node (ref "S5") (pin "C4") (pinfunction "C4_C4") (pintype "passive"))
      (node (ref "S6") (pin "C4") (pinfunction "C4_C4") (pintype "passive"))
      (node (ref "SW_IN") (pin "9") (pinfunction "9_9") (pintype "passive"))
    )
    (net (code "50") (name "Net-(S1-PadC5)") (class "Default")
      (node (ref "S1") (pin "C5") (pinfunction "C5_C5") (pintype "passive"))
      (node (ref "S2") (pin "C5") (pinfunction "C5_C5") (pintype "passive"))
      (node (ref "S3") (pin "C5") (pinfunction "C5_C5") (pintype "passive"))
      (node (ref "S4") (pin "C5") (pinfunction "C5_C5") (pintype "passive"))
      (node (ref "S5") (pin "C5") (pinfunction "C5_C5") (pintype "passive"))
      (node (ref "S6") (pin "C5") (pinfunction "C5_C5") (pintype "passive"))
      (node (ref "SW_IN") (pin "11") (pinfunction "11_11") (pintype "passive"))
    )
    (net (code "51") (name "Net-(S1-PadC6)") (class "Default")
      (node (ref "S1") (pin "C6") (pinfunction "C6_C6") (pintype "passive"))
      (node (ref "S2") (pin "C6") (pinfunction "C6_C6") (pintype "passive"))
      (node (ref "S3") (pin "C6") (pinfunction "C6_C6") (pintype "passive"))
      (node (ref "S4") (pin "C6") (pinfunction "C6_C6") (pintype "passive"))
      (node (ref "S5") (pin "C6") (pinfunction "C6_C6") (pintype "passive"))
      (node (ref "S6") (pin "C6") (pinfunction "C6_C6") (pintype "passive"))
      (node (ref "SW_IN") (pin "13") (pinfunction "13_13") (pintype "passive"))
    )
    (net (code "52") (name "Net-(S2-PadA)") (class "Default")
      (node (ref "S2") (pin "A") (pinfunction "A_A") (pintype "passive"))
      (node (ref "SW_OUT") (pin "6") (pinfunction "6_6") (pintype "passive"))
    )
    (net (code "53") (name "Net-(S2-PadC)") (class "Default")
      (node (ref "S2") (pin "C") (pinfunction "C_C") (pintype "passive"))
      (node (ref "SW_OUT") (pin "5") (pinfunction "5_5") (pintype "passive"))
    )
    (net (code "54") (name "Net-(S3-PadA)") (class "Default")
      (node (ref "S3") (pin "A") (pinfunction "A_A") (pintype "passive"))
      (node (ref "SW_OUT") (pin "8") (pinfunction "8_8") (pintype "passive"))
    )
    (net (code "55") (name "Net-(S3-PadC)") (class "Default")
      (node (ref "S3") (pin "C") (pinfunction "C_C") (pintype "passive"))
      (node (ref "SW_OUT") (pin "7") (pinfunction "7_7") (pintype "passive"))
    )
    (net (code "56") (name "Net-(S4-PadA)") (class "Default")
      (node (ref "S4") (pin "A") (pinfunction "A_A") (pintype "passive"))
      (node (ref "SW_OUT") (pin "10") (pinfunction "10_10") (pintype "passive"))
    )
    (net (code "57") (name "Net-(S4-PadC)") (class "Default")
      (node (ref "S4") (pin "C") (pinfunction "C_C") (pintype "passive"))
      (node (ref "SW_OUT") (pin "9") (pinfunction "9_9") (pintype "passive"))
    )
    (net (code "58") (name "Net-(S5-PadA)") (class "Default")
      (node (ref "S5") (pin "A") (pinfunction "A_A") (pintype "passive"))
      (node (ref "SW_OUT") (pin "12") (pinfunction "12_12") (pintype "passive"))
    )
    (net (code "59") (name "Net-(S5-PadC)") (class "Default")
      (node (ref "S5") (pin "C") (pinfunction "C_C") (pintype "passive"))
      (node (ref "SW_OUT") (pin "11") (pinfunction "11_11") (pintype "passive"))
    )
    (net (code "60") (name "Net-(S6-PadA)") (class "Default")
      (node (ref "S6") (pin "A") (pinfunction "A_A") (pintype "passive"))
      (node (ref "SW_OUT") (pin "14") (pinfunction "14_14") (pintype "passive"))
    )
    (net (code "61") (name "Net-(S6-PadC)") (class "Default")
      (node (ref "S6") (pin "C") (pinfunction "C_C") (pintype "passive"))
      (node (ref "SW_OUT") (pin "13") (pinfunction "13_13") (pintype "passive"))
    )
    (net (code "62") (name "Net-(SW_IN1-Pad1)") (class "Default")
      (node (ref "SW_IN1") (pin "1") (pinfunction "1_1") (pintype "passive"))
      (node (ref "SW_IN1") (pin "2") (pinfunction "2_2") (pintype "passive"))
      (node (ref "U$1") (pin "GND") (pinfunction "GND_GND") (pintype "bidirectional"))
      (node (ref "U$1") (pin "LEFT_OFF") (pinfunction "LEFT_OFF_LEFT_OFF") (pintype "bidirectional"))
      (node (ref "U$1") (pin "RIGHT_OFF") (pinfunction "RIGHT_OFF_RIGHT_OFF") (pintype "bidirectional"))
      (node (ref "U$2") (pin "GND") (pinfunction "GND_GND") (pintype "bidirectional"))
      (node (ref "U$2") (pin "LEFT_OFF") (pinfunction "LEFT_OFF_LEFT_OFF") (pintype "bidirectional"))
      (node (ref "U$2") (pin "RIGHT_OFF") (pinfunction "RIGHT_OFF_RIGHT_OFF") (pintype "bidirectional"))
      (node (ref "U$3") (pin "GND") (pinfunction "GND_GND") (pintype "bidirectional"))
      (node (ref "U$3") (pin "LEFT_OFF") (pinfunction "LEFT_OFF_LEFT_OFF") (pintype "bidirectional"))
      (node (ref "U$3") (pin "RIGHT_OFF") (pinfunction "RIGHT_OFF_RIGHT_OFF") (pintype "bidirectional"))
      (node (ref "U$4") (pin "GND") (pinfunction "GND_GND") (pintype "bidirectional"))
      (node (ref "U$4") (pin "LEFT_OFF") (pinfunction "LEFT_OFF_LEFT_OFF") (pintype "bidirectional"))
      (node (ref "U$4") (pin "RIGHT_OFF") (pinfunction "RIGHT_OFF_RIGHT_OFF") (pintype "bidirectional"))
      (node (ref "U$5") (pin "GND") (pinfunction "GND_GND") (pintype "bidirectional"))
      (node (ref "U$5") (pin "LEFT_OFF") (pinfunction "LEFT_OFF_LEFT_OFF") (pintype "bidirectional"))
      (node (ref "U$5") (pin "RIGHT_OFF") (pinfunction "RIGHT_OFF_RIGHT_OFF") (pintype "bidirectional"))
      (node (ref "U$6") (pin "GND") (pinfunction "GND_GND") (pintype "bidirectional"))
      (node (ref "U$6") (pin "LEFT_OFF") (pinfunction "LEFT_OFF_LEFT_OFF") (pintype "bidirectional"))
      (node (ref "U$6") (pin "RIGHT_OFF") (pinfunction "RIGHT_OFF_RIGHT_OFF") (pintype "bidirectional"))
    )
    (net (code "63") (name "Net-(SW_IN1-Pad3)") (class "Default")
      (node (ref "SW_IN1") (pin "3") (pinfunction "3_3") (pintype "passive"))
      (node (ref "U$1") (pin "LEFT") (pinfunction "LEFT_LEFT") (pintype "bidirectional"))
    )
    (net (code "64") (name "Net-(SW_IN1-Pad4)") (class "Default")
      (node (ref "SW_IN1") (pin "4") (pinfunction "4_4") (pintype "passive"))
      (node (ref "U$1") (pin "RIGHT") (pinfunction "RIGHT_RIGHT") (pintype "bidirectional"))
    )
    (net (code "65") (name "Net-(SW_IN1-Pad5)") (class "Default")
      (node (ref "SW_IN1") (pin "5") (pinfunction "5_5") (pintype "passive"))
      (node (ref "U$2") (pin "LEFT") (pinfunction "LEFT_LEFT") (pintype "bidirectional"))
    )
    (net (code "66") (name "Net-(SW_IN1-Pad6)") (class "Default")
      (node (ref "SW_IN1") (pin "6") (pinfunction "6_6") (pintype "passive"))
      (node (ref "U$2") (pin "RIGHT") (pinfunction "RIGHT_RIGHT") (pintype "bidirectional"))
    )
    (net (code "67") (name "Net-(SW_IN1-Pad7)") (class "Default")
      (node (ref "SW_IN1") (pin "7") (pinfunction "7_7") (pintype "passive"))
      (node (ref "U$3") (pin "LEFT") (pinfunction "LEFT_LEFT") (pintype "bidirectional"))
    )
    (net (code "68") (name "Net-(SW_IN1-Pad8)") (class "Default")
      (node (ref "SW_IN1") (pin "8") (pinfunction "8_8") (pintype "passive"))
      (node (ref "U$3") (pin "RIGHT") (pinfunction "RIGHT_RIGHT") (pintype "bidirectional"))
    )
    (net (code "69") (name "Net-(SW_IN1-Pad9)") (class "Default")
      (node (ref "SW_IN1") (pin "9") (pinfunction "9_9") (pintype "passive"))
      (node (ref "U$4") (pin "LEFT") (pinfunction "LEFT_LEFT") (pintype "bidirectional"))
    )
    (net (code "70") (name "Net-(SW_IN1-Pad10)") (class "Default")
      (node (ref "SW_IN1") (pin "10") (pinfunction "10_10") (pintype "passive"))
      (node (ref "U$4") (pin "RIGHT") (pinfunction "RIGHT_RIGHT") (pintype "bidirectional"))
    )
    (net (code "71") (name "Net-(SW_IN1-Pad11)") (class "Default")
      (node (ref "SW_IN1") (pin "11") (pinfunction "11_11") (pintype "passive"))
      (node (ref "U$5") (pin "LEFT") (pinfunction "LEFT_LEFT") (pintype "bidirectional"))
    )
    (net (code "72") (name "Net-(SW_IN1-Pad12)") (class "Default")
      (node (ref "SW_IN1") (pin "12") (pinfunction "12_12") (pintype "passive"))
      (node (ref "U$5") (pin "RIGHT") (pinfunction "RIGHT_RIGHT") (pintype "bidirectional"))
    )
    (net (code "73") (name "Net-(SW_IN1-Pad13)") (class "Default")
      (node (ref "SW_IN1") (pin "13") (pinfunction "13_13") (pintype "passive"))
      (node (ref "U$6") (pin "LEFT") (pinfunction "LEFT_LEFT") (pintype "bidirectional"))
    )
    (net (code "74") (name "Net-(SW_IN1-Pad14)") (class "Default")
      (node (ref "SW_IN1") (pin "14") (pinfunction "14_14") (pintype "passive"))
      (node (ref "U$6") (pin "RIGHT") (pinfunction "RIGHT_RIGHT") (pintype "bidirectional"))
    )
    (net (code "75") (name "Net-(SW_IN2-Pad1)") (class "Default")
      (node (ref "SW_IN2") (pin "1") (pinfunction "1_1") (pintype "passive"))
      (node (ref "SW_IN2") (pin "2") (pinfunction "2_2") (pintype "passive"))
      (node (ref "U$10") (pin "GND") (pinfunction "GND_GND") (pintype "bidirectional"))
      (node (ref "U$10") (pin "LEFT_OFF") (pinfunction "LEFT_OFF_LEFT_OFF") (pintype "bidirectional"))
      (node (ref "U$10") (pin "RIGHT_OFF") (pinfunction "RIGHT_OFF_RIGHT_OFF") (pintype "bidirectional"))
      (node (ref "U$11") (pin "GND") (pinfunction "GND_GND") (pintype "bidirectional"))
      (node (ref "U$11") (pin "LEFT_OFF") (pinfunction "LEFT_OFF_LEFT_OFF") (pintype "bidirectional"))
      (node (ref "U$11") (pin "RIGHT_OFF") (pinfunction "RIGHT_OFF_RIGHT_OFF") (pintype "bidirectional"))
      (node (ref "U$12") (pin "GND") (pinfunction "GND_GND") (pintype "bidirectional"))
      (node (ref "U$12") (pin "LEFT_OFF") (pinfunction "LEFT_OFF_LEFT_OFF") (pintype "bidirectional"))
      (node (ref "U$12") (pin "RIGHT_OFF") (pinfunction "RIGHT_OFF_RIGHT_OFF") (pintype "bidirectional"))
      (node (ref "U$7") (pin "GND") (pinfunction "GND_GND") (pintype "bidirectional"))
      (node (ref "U$7") (pin "LEFT_OFF") (pinfunction "LEFT_OFF_LEFT_OFF") (pintype "bidirectional"))
      (node (ref "U$7") (pin "RIGHT_OFF") (pinfunction "RIGHT_OFF_RIGHT_OFF") (pintype "bidirectional"))
      (node (ref "U$8") (pin "GND") (pinfunction "GND_GND") (pintype "bidirectional"))
      (node (ref "U$8") (pin "LEFT_OFF") (pinfunction "LEFT_OFF_LEFT_OFF") (pintype "bidirectional"))
      (node (ref "U$8") (pin "RIGHT_OFF") (pinfunction "RIGHT_OFF_RIGHT_OFF") (pintype "bidirectional"))
      (node (ref "U$9") (pin "GND") (pinfunction "GND_GND") (pintype "bidirectional"))
      (node (ref "U$9") (pin "LEFT_OFF") (pinfunction "LEFT_OFF_LEFT_OFF") (pintype "bidirectional"))
      (node (ref "U$9") (pin "RIGHT_OFF") (pinfunction "RIGHT_OFF_RIGHT_OFF") (pintype "bidirectional"))
    )
    (net (code "76") (name "Net-(SW_IN2-Pad3)") (class "Default")
      (node (ref "SW_IN2") (pin "3") (pinfunction "3_3") (pintype "passive"))
      (node (ref "U$7") (pin "LEFT") (pinfunction "LEFT_LEFT") (pintype "bidirectional"))
    )
    (net (code "77") (name "Net-(SW_IN2-Pad4)") (class "Default")
      (node (ref "SW_IN2") (pin "4") (pinfunction "4_4") (pintype "passive"))
      (node (ref "U$7") (pin "RIGHT") (pinfunction "RIGHT_RIGHT") (pintype "bidirectional"))
    )
    (net (code "78") (name "Net-(SW_IN2-Pad5)") (class "Default")
      (node (ref "SW_IN2") (pin "5") (pinfunction "5_5") (pintype "passive"))
      (node (ref "U$8") (pin "LEFT") (pinfunction "LEFT_LEFT") (pintype "bidirectional"))
    )
    (net (code "79") (name "Net-(SW_IN2-Pad6)") (class "Default")
      (node (ref "SW_IN2") (pin "6") (pinfunction "6_6") (pintype "passive"))
      (node (ref "U$8") (pin "RIGHT") (pinfunction "RIGHT_RIGHT") (pintype "bidirectional"))
    )
    (net (code "80") (name "Net-(SW_IN2-Pad7)") (class "Default")
      (node (ref "SW_IN2") (pin "7") (pinfunction "7_7") (pintype "passive"))
      (node (ref "U$9") (pin "LEFT") (pinfunction "LEFT_LEFT") (pintype "bidirectional"))
    )
    (net (code "81") (name "Net-(SW_IN2-Pad8)") (class "Default")
      (node (ref "SW_IN2") (pin "8") (pinfunction "8_8") (pintype "passive"))
      (node (ref "U$9") (pin "RIGHT") (pinfunction "RIGHT_RIGHT") (pintype "bidirectional"))
    )
    (net (code "82") (name "Net-(SW_IN2-Pad9)") (class "Default")
      (node (ref "SW_IN2") (pin "9") (pinfunction "9_9") (pintype "passive"))
      (node (ref "U$10") (pin "LEFT") (pinfunction "LEFT_LEFT") (pintype "bidirectional"))
    )
    (net (code "83") (name "Net-(SW_IN2-Pad10)") (class "Default")
      (node (ref "SW_IN2") (pin "10") (pinfunction "10_10") (pintype "passive"))
      (node (ref "U$10") (pin "RIGHT") (pinfunction "RIGHT_RIGHT") (pintype "bidirectional"))
    )
    (net (code "84") (name "Net-(SW_IN2-Pad11)") (class "Default")
      (node (ref "SW_IN2") (pin "11") (pinfunction "11_11") (pintype "passive"))
      (node (ref "U$11") (pin "LEFT") (pinfunction "LEFT_LEFT") (pintype "bidirectional"))
    )
    (net (code "85") (name "Net-(SW_IN2-Pad12)") (class "Default")
      (node (ref "SW_IN2") (pin "12") (pinfunction "12_12") (pintype "passive"))
      (node (ref "U$11") (pin "RIGHT") (pinfunction "RIGHT_RIGHT") (pintype "bidirectional"))
    )
    (net (code "86") (name "Net-(SW_IN2-Pad13)") (class "Default")
      (node (ref "SW_IN2") (pin "13") (pinfunction "13_13") (pintype "passive"))
      (node (ref "U$12") (pin "LEFT") (pinfunction "LEFT_LEFT") (pintype "bidirectional"))
    )
    (net (code "87") (name "Net-(SW_IN2-Pad14)") (class "Default")
      (node (ref "SW_IN2") (pin "14") (pinfunction "14_14") (pintype "passive"))
      (node (ref "U$12") (pin "RIGHT") (pinfunction "RIGHT_RIGHT") (pintype "bidirectional"))
    )
    (net (code "88") (name "Net-(X14A-KL)") (class "Default")
      (node (ref "TR1") (pin "1") (pinfunction "1_1") (pintype "passive"))
      (node (ref "X14") (pin "1") (pinfunction "KL_1") (pintype "passive"))
    )
    (net (code "89") (name "Net-(X14B-KL)") (class "Default")
      (node (ref "TR1") (pin "4") (pinfunction "4_4") (pintype "passive"))
      (node (ref "X14") (pin "2") (pinfunction "KL_2") (pintype "passive"))
    )
  )
)
